# 02_Power.net
KiCad netlist of a schematic drawn in Altium Designer
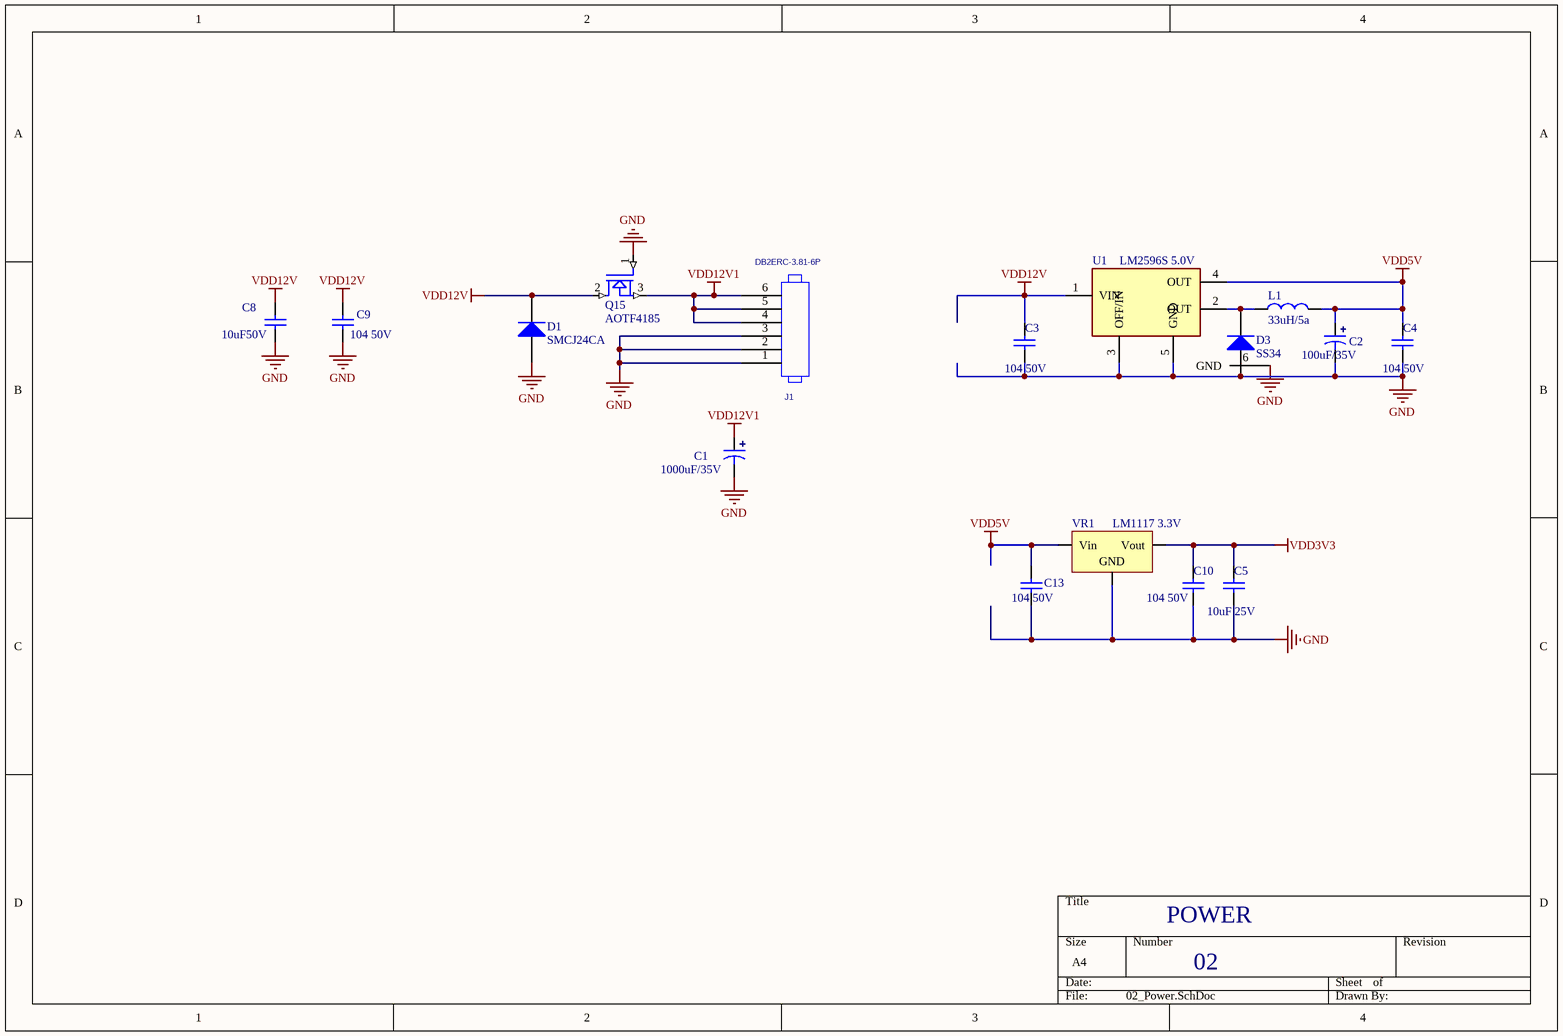
[diagram p0: 02_Power.SchDoc]

(export (version "E")
  (design (tool "Eeschema 10.0.6"))
  (components
    (comp (ref "C1")
      (value "1000uF/35V")
      (footprint "10*16")
      (description "电解电容")
      (libsource (lib "XiaoyI") (part "CAP2"))
    )
    (comp (ref "C2")
      (value "100uF/35V")
      (footprint "6*8")
      (description "电解电容")
      (libsource (lib "XiaoyI") (part "CAP2"))
    )
    (comp (ref "C3")
      (value "104 50V")
      (footprint "SMD-0603C")
      (description "贴片电容 10%")
      (libsource (lib "XiaoyI") (part "CAP4"))
    )
    (comp (ref "C4")
      (value "104 50V")
      (footprint "SMD-0603C")
      (description "贴片电容 10%")
      (libsource (lib "XiaoyI") (part "CAP4"))
    )
    (comp (ref "C5")
      (value "10uF 25V")
      (footprint "SMD-0805C")
      (description "贴片电容 20%")
      (libsource (lib "XiaoyI") (part "CAP4"))
    )
    (comp (ref "C8")
      (value "10uF50V")
      (footprint "SMD-0805C")
      (description "贴片电容 10%")
      (libsource (lib "XiaoyI") (part "CAP4"))
    )
    (comp (ref "C9")
      (value "104 50V")
      (footprint "SMD-0603C")
      (description "贴片电容 10%")
      (libsource (lib "XiaoyI") (part "CAP4"))
    )
    (comp (ref "C10")
      (value "104 50V")
      (footprint "SMD-0603C")
      (description "贴片电容 10%")
      (libsource (lib "XiaoyI") (part "CAP4"))
    )
    (comp (ref "C13")
      (value "104 50V")
      (footprint "SMD-0603C")
      (description "贴片电容 10%")
      (libsource (lib "XiaoyI") (part "CAP4"))
    )
    (comp (ref "D1")
      (value "SMCJ24CA")
      (footprint "Pcblib_20110825:SMC")
      (libsource (lib "Sch_library") (part "DIODE"))
    )
    (comp (ref "D3") (value "SS34") (footprint "SMA") (libsource (lib "Sch_library") (part "DIODE")))
    (comp (ref "J1")
      (value "DB2ERC-3.81-6P")
      (footprint "VH-AW-3.96*6P")
      (fields (field (name "Comment") "HEADER_6"))
      (libsource (lib "liujingtao_V1.0") (part "HEADER_6"))
    )
    (comp (ref "L1") (value "33uH/5a") (footprint "CDRH-127") (libsource (lib "Sch_library") (part "IND")))
    (comp (ref "Q15")
      (value "AOTF4185")
      (footprint "Pcblib_20110825:to220")
      (description "MOSFET N")
      (libsource (lib "XiaoyI") (part "MOSFET N"))
    )
    (comp (ref "U1")
      (value "LM2596S 5.0V")
      (footprint "TO-263-5")
      (libsource (lib "Sch_library") (part "LM2596"))
    )
    (comp (ref "VR1")
      (value "LM1117 3.3V")
      (footprint "SOT223")
      (description "三端稳压器")
      (libsource (lib "XiaoyI") (part "LM1117"))
    )
  )
  (nets
    (net (code "1") (name "GND") (class "Default")
      (node (ref "C1") (pin "2") (pinfunction "2_2") (pintype "passive"))
      (node (ref "C10") (pin "1") (pinfunction "1_1") (pintype "passive"))
      (node (ref "C13") (pin "1") (pinfunction "1_1") (pintype "passive"))
      (node (ref "C2") (pin "2") (pinfunction "2_2") (pintype "passive"))
      (node (ref "C3") (pin "1") (pinfunction "1_1") (pintype "passive"))
      (node (ref "C4") (pin "1") (pinfunction "1_1") (pintype "passive"))
      (node (ref "C5") (pin "1") (pinfunction "1_1") (pintype "passive"))
      (node (ref "C8") (pin "1") (pinfunction "1_1") (pintype "passive"))
      (node (ref "C9") (pin "1") (pinfunction "1_1") (pintype "passive"))
      (node (ref "D1") (pin "1") (pinfunction "A_1") (pintype "passive"))
      (node (ref "D3") (pin "1") (pinfunction "A_1") (pintype "passive"))
      (node (ref "J1") (pin "1") (pinfunction "1_1") (pintype "passive"))
      (node (ref "J1") (pin "2") (pinfunction "2_2") (pintype "passive"))
      (node (ref "J1") (pin "3") (pinfunction "3_3") (pintype "passive"))
      (node (ref "Q15") (pin "1") (pinfunction "G_1") (pintype "input"))
      (node (ref "U1") (pin "3") (pinfunction "OFF/IN_3") (pintype "passive"))
      (node (ref "U1") (pin "5") (pinfunction "GND_5") (pintype "passive"))
      (node (ref "U1") (pin "6") (pinfunction "GND_6") (pintype "passive"))
      (node (ref "VR1") (pin "1") (pinfunction "GND_1") (pintype "passive"))
    )
    (net (code "2") (name "Net-(D3-K)") (class "Default")
      (node (ref "D3") (pin "2") (pinfunction "K_2") (pintype "passive"))
      (node (ref "L1") (pin "1") (pinfunction "1_1") (pintype "passive"))
      (node (ref "U1") (pin "2") (pinfunction "OUT_2") (pintype "passive"))
    )
    (net (code "3") (name "VDD3V3") (class "Default")
      (node (ref "C10") (pin "2") (pinfunction "2_2") (pintype "passive"))
      (node (ref "C5") (pin "2") (pinfunction "2_2") (pintype "passive"))
      (node (ref "VR1") (pin "2") (pinfunction "Vout_2") (pintype "passive"))
    )
    (net (code "4") (name "VDD5V") (class "Default")
      (node (ref "C13") (pin "2") (pinfunction "2_2") (pintype "passive"))
      (node (ref "C2") (pin "1") (pinfunction "1_1") (pintype "passive"))
      (node (ref "C4") (pin "2") (pinfunction "2_2") (pintype "passive"))
      (node (ref "L1") (pin "2") (pinfunction "2_2") (pintype "passive"))
      (node (ref "U1") (pin "4") (pinfunction "OUT_4") (pintype "passive"))
      (node (ref "VR1") (pin "3") (pinfunction "Vin_3") (pintype "passive"))
    )
    (net (code "5") (name "VDD12V") (class "Default")
      (node (ref "C3") (pin "2") (pinfunction "2_2") (pintype "passive"))
      (node (ref "C8") (pin "2") (pinfunction "2_2") (pintype "passive"))
      (node (ref "C9") (pin "2") (pinfunction "2_2") (pintype "passive"))
      (node (ref "D1") (pin "2") (pinfunction "K_2") (pintype "passive"))
      (node (ref "Q15") (pin "2") (pinfunction "D_2") (pintype "input"))
      (node (ref "U1") (pin "1") (pinfunction "VIN_1") (pintype "passive"))
    )
    (net (code "6") (name "VDD12V1") (class "Default")
      (node (ref "C1") (pin "1") (pinfunction "1_1") (pintype "passive"))
      (node (ref "J1") (pin "4") (pinfunction "4_4") (pintype "passive"))
      (node (ref "J1") (pin "5") (pinfunction "5_5") (pintype "passive"))
      (node (ref "J1") (pin "6") (pinfunction "6_6") (pintype "passive"))
      (node (ref "Q15") (pin "3") (pinfunction "S_3") (pintype "output"))
    )
  )
)
